# EVK-NORA-W1_SCHEM_0004_Interface_FTDI.net
KiCad netlist of a schematic drawn in Altium Designer
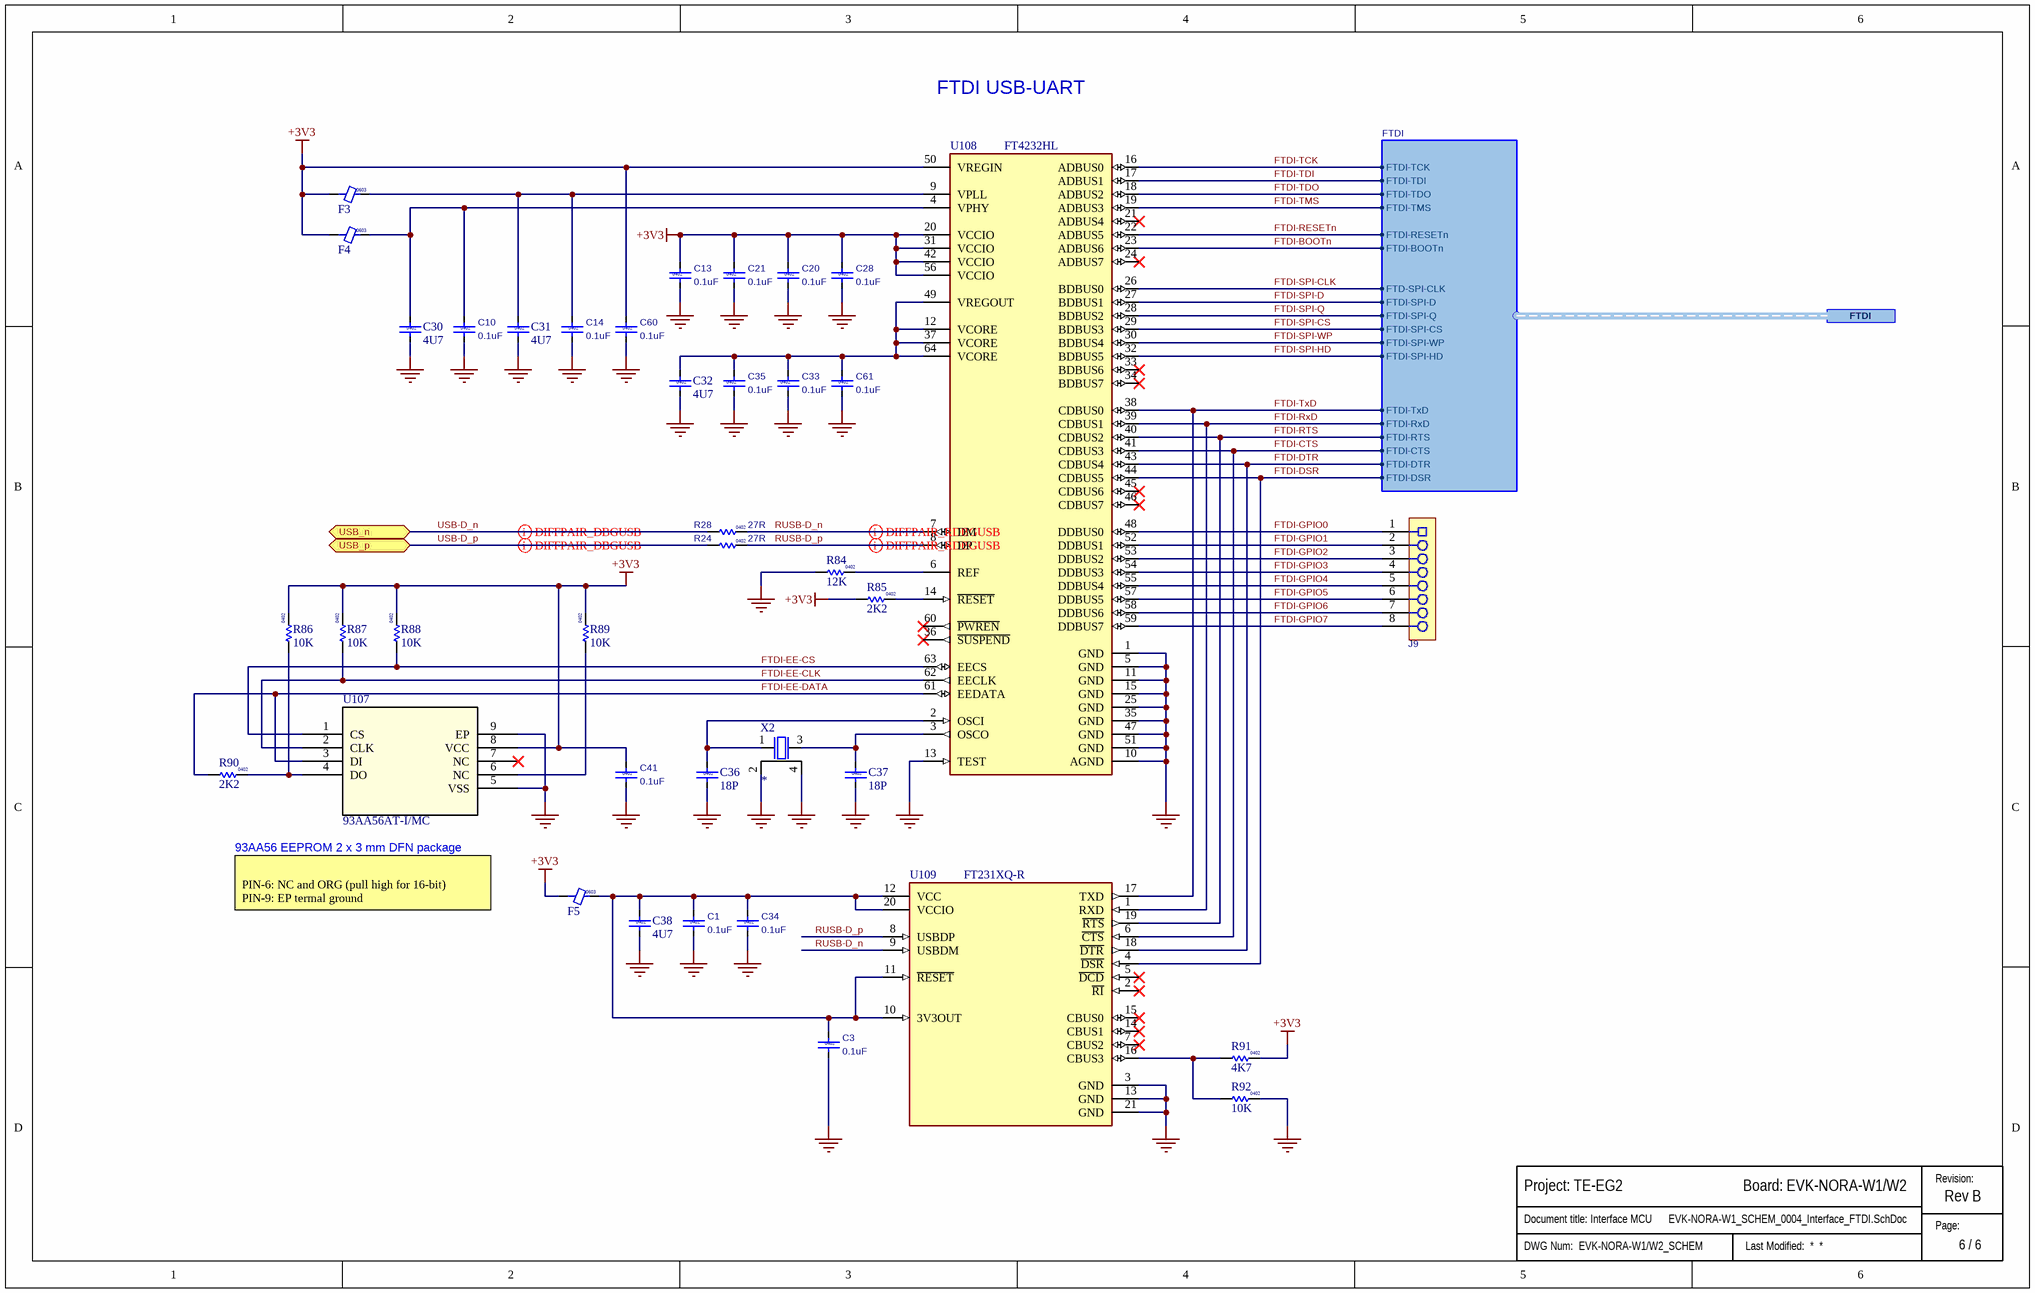
[diagram p0: EVK-NORA-W1_SCHEM_0004_Interface_FTDI.SchDoc]

(export (version "E")
  (design (tool "Eeschema 10.0.6"))
  (components
    (comp (ref "C1")
      (value "0.1uF")
      (footprint "Cap 0402 HD")
      (description "Cap, Ceramic 0.1uF 10V 10% X5R 0402")
      (fields
        (field (name "SIZE") "0402")
        (field (name "PART NUMBER") "120-00016")
        (field (name "MANUFACTURER") "Murata Electronics North America")
      )
      (libsource (lib "Arena_Parts_DB_Lib") (part "Cap Chip"))
    )
    (comp (ref "C3")
      (value "0.1uF")
      (footprint "Cap 0402 HD")
      (description "Cap, Ceramic 0.1uF 10V 10% X5R 0402")
      (fields
        (field (name "SIZE") "0402")
        (field (name "PART NUMBER") "120-00016")
        (field (name "MANUFACTURER") "Murata Electronics North America")
      )
      (libsource (lib "Arena_Parts_DB_Lib") (part "Cap Chip"))
    )
    (comp (ref "C10")
      (value "0.1uF")
      (footprint "Cap 0402 HD")
      (description "Cap, Ceramic 0.1uF 10V 10% X5R 0402")
      (fields
        (field (name "SIZE") "0402")
        (field (name "PART NUMBER") "120-00016")
        (field (name "MANUFACTURER") "Murata Electronics North America")
      )
      (libsource (lib "Arena_Parts_DB_Lib") (part "Cap Chip"))
    )
    (comp (ref "C13")
      (value "0.1uF")
      (footprint "Cap 0402 HD")
      (description "Cap, Ceramic 0.1uF 10V 10% X5R 0402")
      (fields
        (field (name "SIZE") "0402")
        (field (name "PART NUMBER") "120-00016")
        (field (name "MANUFACTURER") "Murata Electronics North America")
      )
      (libsource (lib "Arena_Parts_DB_Lib") (part "Cap Chip"))
    )
    (comp (ref "C14")
      (value "0.1uF")
      (footprint "Cap 0402 HD")
      (description "Cap, Ceramic 0.1uF 10V 10% X5R 0402")
      (fields
        (field (name "SIZE") "0402")
        (field (name "PART NUMBER") "120-00016")
        (field (name "MANUFACTURER") "Murata Electronics North America")
      )
      (libsource (lib "Arena_Parts_DB_Lib") (part "Cap Chip"))
    )
    (comp (ref "C20")
      (value "0.1uF")
      (footprint "Cap 0402 HD")
      (description "Cap, Ceramic 0.1uF 10V 10% X5R 0402")
      (fields
        (field (name "SIZE") "0402")
        (field (name "PART NUMBER") "120-00016")
        (field (name "MANUFACTURER") "Murata Electronics North America")
      )
      (libsource (lib "Arena_Parts_DB_Lib") (part "Cap Chip"))
    )
    (comp (ref "C21")
      (value "0.1uF")
      (footprint "Cap 0402 HD")
      (description "Cap, Ceramic 0.1uF 10V 10% X5R 0402")
      (fields
        (field (name "SIZE") "0402")
        (field (name "PART NUMBER") "120-00016")
        (field (name "MANUFACTURER") "Murata Electronics North America")
      )
      (libsource (lib "Arena_Parts_DB_Lib") (part "Cap Chip"))
    )
    (comp (ref "C28")
      (value "0.1uF")
      (footprint "Cap 0402 HD")
      (description "Cap, Ceramic 0.1uF 10V 10% X5R 0402")
      (fields
        (field (name "SIZE") "0402")
        (field (name "PART NUMBER") "120-00016")
        (field (name "MANUFACTURER") "Murata Electronics North America")
      )
      (libsource (lib "Arena_Parts_DB_Lib") (part "Cap Chip"))
    )
    (comp (ref "C30")
      (value "4U7")
      (footprint "Cap 0402 HD")
      (description "CAP CER X5R 0402 4U7 20% 10V")
      (fields
        (field (name "SIZE") "0402")
        (field (name "PART NUMBER") "UBXH01-0000243")
        (field (name "TOLERANCE") "20%")
        (field (name "EDITOR") "martin.pilik")
        (field (name "RELEASED BY") "fabrice.bret-dibat")
      )
      (libsource (lib "UBX_Parts_DB_Lib") (part "Cap Chip"))
    )
    (comp (ref "C31")
      (value "4U7")
      (footprint "Cap 0402 HD")
      (description "CAP CER X5R 0402 4U7 20% 10V")
      (fields
        (field (name "SIZE") "0402")
        (field (name "PART NUMBER") "UBXH01-0000243")
        (field (name "TOLERANCE") "20%")
        (field (name "EDITOR") "martin.pilik")
        (field (name "RELEASED BY") "fabrice.bret-dibat")
      )
      (libsource (lib "UBX_Parts_DB_Lib") (part "Cap Chip"))
    )
    (comp (ref "C32")
      (value "4U7")
      (footprint "Cap 0402 HD")
      (description "CAP CER X5R 0402 4U7 20% 10V")
      (fields
        (field (name "SIZE") "0402")
        (field (name "PART NUMBER") "UBXH01-0000243")
        (field (name "TOLERANCE") "20%")
        (field (name "EDITOR") "martin.pilik")
        (field (name "RELEASED BY") "fabrice.bret-dibat")
      )
      (libsource (lib "UBX_Parts_DB_Lib") (part "Cap Chip"))
    )
    (comp (ref "C33")
      (value "0.1uF")
      (footprint "Cap 0402 HD")
      (description "Cap, Ceramic 0.1uF 10V 10% X5R 0402")
      (fields
        (field (name "SIZE") "0402")
        (field (name "PART NUMBER") "120-00016")
        (field (name "MANUFACTURER") "Murata Electronics North America")
      )
      (libsource (lib "Arena_Parts_DB_Lib") (part "Cap Chip"))
    )
    (comp (ref "C34")
      (value "0.1uF")
      (footprint "Cap 0402 HD")
      (description "Cap, Ceramic 0.1uF 10V 10% X5R 0402")
      (fields
        (field (name "SIZE") "0402")
        (field (name "PART NUMBER") "120-00016")
        (field (name "MANUFACTURER") "Murata Electronics North America")
      )
      (libsource (lib "Arena_Parts_DB_Lib") (part "Cap Chip"))
    )
    (comp (ref "C35")
      (value "0.1uF")
      (footprint "Cap 0402 HD")
      (description "Cap, Ceramic 0.1uF 10V 10% X5R 0402")
      (fields
        (field (name "SIZE") "0402")
        (field (name "PART NUMBER") "120-00016")
        (field (name "MANUFACTURER") "Murata Electronics North America")
      )
      (libsource (lib "Arena_Parts_DB_Lib") (part "Cap Chip"))
    )
    (comp (ref "C36")
      (value "18P")
      (footprint "Cap 0402")
      (description "CAP CER C0G 0402 18P 5% 25V")
      (fields
        (field (name "SIZE") "0402")
        (field (name "PART NUMBER") "UBXH01-0004017")
        (field (name "TOLERANCE") "5%")
        (field (name "EDITOR") "doris.zahnd")
        (field (name "RELEASED BY") "daniel.hurni")
      )
      (libsource (lib "UBX_Parts_DB_Lib") (part "Cap Chip"))
    )
    (comp (ref "C37")
      (value "18P")
      (footprint "Cap 0402")
      (description "CAP CER C0G 0402 18P 5% 25V")
      (fields
        (field (name "SIZE") "0402")
        (field (name "PART NUMBER") "UBXH01-0004017")
        (field (name "TOLERANCE") "5%")
        (field (name "EDITOR") "doris.zahnd")
        (field (name "RELEASED BY") "daniel.hurni")
      )
      (libsource (lib "UBX_Parts_DB_Lib") (part "Cap Chip"))
    )
    (comp (ref "C38")
      (value "4U7")
      (footprint "Cap 0402 HD")
      (description "CAP CER X5R 0402 4U7 20% 10V")
      (fields
        (field (name "SIZE") "0402")
        (field (name "PART NUMBER") "UBXH01-0000243")
        (field (name "TOLERANCE") "20%")
        (field (name "EDITOR") "martin.pilik")
        (field (name "RELEASED BY") "fabrice.bret-dibat")
      )
      (libsource (lib "UBX_Parts_DB_Lib") (part "Cap Chip"))
    )
    (comp (ref "C41")
      (value "0.1uF")
      (footprint "Cap 0402 HD")
      (description "Cap, Ceramic 0.1uF 10V 10% X5R 0402")
      (fields
        (field (name "SIZE") "0402")
        (field (name "PART NUMBER") "120-00016")
        (field (name "MANUFACTURER") "Murata Electronics North America")
      )
      (libsource (lib "Arena_Parts_DB_Lib") (part "Cap Chip"))
    )
    (comp (ref "C60")
      (value "0.1uF")
      (footprint "Cap 0402 HD")
      (description "Cap, Ceramic 0.1uF 10V 10% X5R 0402")
      (fields
        (field (name "SIZE") "0402")
        (field (name "PART NUMBER") "120-00016")
        (field (name "MANUFACTURER") "Murata Electronics North America")
      )
      (libsource (lib "Arena_Parts_DB_Lib") (part "Cap Chip"))
    )
    (comp (ref "C61")
      (value "0.1uF")
      (footprint "Cap 0402 HD")
      (description "Cap, Ceramic 0.1uF 10V 10% X5R 0402")
      (fields
        (field (name "SIZE") "0402")
        (field (name "PART NUMBER") "120-00016")
        (field (name "MANUFACTURER") "Murata Electronics North America")
      )
      (libsource (lib "Arena_Parts_DB_Lib") (part "Cap Chip"))
    )
    (comp (ref "F3")
      (value "UBXH08-0000001")
      (footprint "IND 0603 HD")
      (description "FERRITE BEAD 0603 600 OHM AT 100MHZ 600OHM 500mA")
      (fields
        (field (name "SIZE") "0603")
        (field (name "MANUFACTURER") "TDK Corporation")
        (field (name "EDITOR") "daniel.hurni")
        (field (name "RELEASED BY") "martin.frauchiger")
      )
      (libsource (lib "UBX_Parts_DB_Lib") (part "FB sm"))
    )
    (comp (ref "F4")
      (value "UBXH08-0000001")
      (footprint "IND 0603 HD")
      (description "FERRITE BEAD 0603 600 OHM AT 100MHZ 600OHM 500mA")
      (fields
        (field (name "SIZE") "0603")
        (field (name "MANUFACTURER") "TDK Corporation")
        (field (name "EDITOR") "daniel.hurni")
        (field (name "RELEASED BY") "martin.frauchiger")
      )
      (libsource (lib "UBX_Parts_DB_Lib") (part "FB sm"))
    )
    (comp (ref "F5")
      (value "UBXH08-0000001")
      (footprint "IND 0603 HD")
      (description "FERRITE BEAD 0603 600 OHM AT 100MHZ 600OHM 500mA")
      (fields
        (field (name "SIZE") "0603")
        (field (name "MANUFACTURER") "TDK Corporation")
        (field (name "EDITOR") "daniel.hurni")
        (field (name "RELEASED BY") "martin.frauchiger")
      )
      (libsource (lib "UBX_Parts_DB_Lib") (part "FB sm"))
    )
    (comp (ref "J9")
      (value "130-00102")
      (footprint "SKT-0.1P-SSM-108-L-SV")
      (description "Socket Strip 0.1\" 8 Pin 1Row SMD Black")
      (fields (field (name "VOLTAGE") "572VDC"))
      (libsource (lib "Arena_Parts_DB_Lib") (part "CON-8Pin_1Row"))
    )
    (comp (ref "R24")
      (value "27R")
      (footprint "RES 0402 HD")
      (description "Resistor, 27ohm, 1%, 1/16W, 0402")
      (fields
        (field (name "SIZE") "0402")
        (field (name "PART NUMBER") "180-00125")
        (field (name "MANUFACTURER") "Panasonic Electronic Components")
      )
      (libsource (lib "Arena_Parts_DB_Lib") (part "Res sm"))
    )
    (comp (ref "R28")
      (value "27R")
      (footprint "RES 0402 HD")
      (description "Resistor, 27ohm, 1%, 1/16W, 0402")
      (fields
        (field (name "SIZE") "0402")
        (field (name "PART NUMBER") "180-00125")
        (field (name "MANUFACTURER") "Panasonic Electronic Components")
      )
      (libsource (lib "Arena_Parts_DB_Lib") (part "Res sm"))
    )
    (comp (ref "R84")
      (value "12K")
      (footprint "RES 0402 HD")
      (description "RES THICK FILM CHIP 0402 12K 1% 63mW")
      (fields
        (field (name "SIZE") "0402")
        (field (name "PART NUMBER") "UBXH18-0000137")
        (field (name "TOLERANCE") "1%")
        (field (name "EDITOR") "matej.budin")
        (field (name "RELEASED BY") "gabriele.capello")
      )
      (libsource (lib "UBX_Parts_DB_Lib") (part "Res sm"))
    )
    (comp (ref "R85")
      (value "2K2")
      (footprint "RES 0402 HD")
      (description "RES THICK FILM CHIP 0402 2K2 5% 100mW")
      (fields
        (field (name "SIZE") "0402")
        (field (name "PART NUMBER") "UBXH18-0008057")
        (field (name "TOLERANCE") "5%")
        (field (name "EDITOR") "roland.rust")
        (field (name "RELEASED BY") "roland.rust")
      )
      (libsource (lib "UBX_Parts_DB_Lib") (part "Res sm"))
    )
    (comp (ref "R86")
      (value "10K")
      (footprint "RES 0402 HD")
      (description "RES THICK FILM CHIP 0402 10K 5% 100mW")
      (fields
        (field (name "SIZE") "0402")
        (field (name "PART NUMBER") "UBXH18-0008073")
        (field (name "TOLERANCE") "5%")
        (field (name "EDITOR") "martin.frauchiger")
        (field (name "RELEASED BY") "martin.frauchiger")
      )
      (libsource (lib "UBX_Parts_DB_Lib") (part "Res sm"))
    )
    (comp (ref "R87")
      (value "10K")
      (footprint "RES 0402 HD")
      (description "RES THICK FILM CHIP 0402 10K 5% 100mW")
      (fields
        (field (name "SIZE") "0402")
        (field (name "PART NUMBER") "UBXH18-0008073")
        (field (name "TOLERANCE") "5%")
        (field (name "EDITOR") "martin.frauchiger")
        (field (name "RELEASED BY") "martin.frauchiger")
      )
      (libsource (lib "UBX_Parts_DB_Lib") (part "Res sm"))
    )
    (comp (ref "R88")
      (value "10K")
      (footprint "RES 0402 HD")
      (description "RES THICK FILM CHIP 0402 10K 5% 100mW")
      (fields
        (field (name "SIZE") "0402")
        (field (name "PART NUMBER") "UBXH18-0008073")
        (field (name "TOLERANCE") "5%")
        (field (name "EDITOR") "martin.frauchiger")
        (field (name "RELEASED BY") "martin.frauchiger")
      )
      (libsource (lib "UBX_Parts_DB_Lib") (part "Res sm"))
    )
    (comp (ref "R89")
      (value "10K")
      (footprint "RES 0402 HD")
      (description "RES THICK FILM CHIP 0402 10K 5% 100mW")
      (fields
        (field (name "SIZE") "0402")
        (field (name "PART NUMBER") "UBXH18-0008073")
        (field (name "TOLERANCE") "5%")
        (field (name "EDITOR") "martin.frauchiger")
        (field (name "RELEASED BY") "martin.frauchiger")
      )
      (libsource (lib "UBX_Parts_DB_Lib") (part "Res sm"))
    )
    (comp (ref "R90")
      (value "2K2")
      (footprint "RES 0402 HD")
      (description "RES THICK FILM CHIP 0402 2K2 5% 100mW")
      (fields
        (field (name "SIZE") "0402")
        (field (name "PART NUMBER") "UBXH18-0008057")
        (field (name "TOLERANCE") "5%")
        (field (name "EDITOR") "roland.rust")
        (field (name "RELEASED BY") "roland.rust")
      )
      (libsource (lib "UBX_Parts_DB_Lib") (part "Res sm"))
    )
    (comp (ref "R91")
      (value "4K7")
      (footprint "RES 0402 HD")
      (description "RES THICK FILM CHIP 0402 4K7 5% 100mW")
      (fields
        (field (name "SIZE") "0402")
        (field (name "PART NUMBER") "UBXH18-0008065")
        (field (name "TOLERANCE") "5%")
        (field (name "EDITOR") "martin.frauchiger")
        (field (name "RELEASED BY") "martin.frauchiger")
      )
      (libsource (lib "UBX_Parts_DB_Lib") (part "Res sm"))
    )
    (comp (ref "R92")
      (value "10K")
      (footprint "RES 0402 HD")
      (description "RES THICK FILM CHIP 0402 10K 5% 100mW")
      (fields
        (field (name "SIZE") "0402")
        (field (name "PART NUMBER") "UBXH18-0008073")
        (field (name "TOLERANCE") "5%")
        (field (name "EDITOR") "martin.frauchiger")
        (field (name "RELEASED BY") "martin.frauchiger")
      )
      (libsource (lib "UBX_Parts_DB_Lib") (part "Res sm"))
    )
    (comp (ref "U107")
      (value "93AA56AT-I/MC")
      (footprint "DFN0.5P-8Pin_W-Pad")
      (description "EEPROM SERIAL 2KBIT 256 X 8 1.8-5.5V DFN-8PIN-2X3MM 5.5V")
      (fields
        (field (name "PART NUMBER") "UBXH13-0000121")
        (field (name "MANUFACTURER") "Microchip")
        (field (name "COPYRIGHT") "Copyright (C) 2022 Ultra Librarian. All rights reserved.")
        (field (name "EDITOR") "hakan.ekfors")
      )
      (libsource (lib "UBX_Parts_DB_Lib") (part "93AA56AT_8pin_IMC"))
    )
    (comp (ref "U108")
      (value "FT4232HL")
      (footprint "QFP0.5P16x16-64Pin_HD")
      (description "FTDI FT4232HL QUAD HIGH SPEED USB TO MULTIPURPOSE UART LQFP-64")
      (fields
        (field (name "PART NUMBER") "UBXH10-0000092")
        (field (name "MANUFACTURER") "FTDI Future Technology Devices International")
        (field (name "EDITOR") "olof.viklund")
        (field (name "RELEASED BY") "aneeb.sohail")
      )
      (libsource (lib "UBX_Parts_DB_Lib") (part "FT4232HL"))
    )
    (comp (ref "U109")
      (value "FT231XQ-R")
      (footprint "QFN_5x5_FT231XQ")
      (description "FTDI USB TO SERIAL FULL UART INTERFACE QFN20")
      (fields
        (field (name "PART NUMBER") "UBXH10-0000054")
        (field (name "MANUFACTURER") "FTDI Future Technology Devices International")
        (field (name "EDITOR") "adam.johansson")
      )
      (libsource (lib "UBX_Parts_DB_Lib") (part "FT231XQ-R"))
    )
    (comp (ref "X2")
      (value "100-00006")
      (footprint "XTAL_3225")
      (description "XTAL, 4Pin, 12.0000MHz, 18pF, 20ppm, 4Pins")
      (fields (field (name "ALTIUM_VALUE") "*") (field (name "VOLTAGE") "None"))
      (libsource (lib "Arena_Parts_DB_Lib") (part "XTAL_4Pin"))
    )
  )
  (nets
    (net (code "2") (name "+3V3") (class "Default")
      (node (ref "C13") (pin "1") (pinfunction "1_1") (pintype "passive"))
      (node (ref "C20") (pin "1") (pinfunction "1_1") (pintype "passive"))
      (node (ref "C21") (pin "1") (pinfunction "1_1") (pintype "passive"))
      (node (ref "C28") (pin "1") (pinfunction "1_1") (pintype "passive"))
      (node (ref "C41") (pin "1") (pinfunction "1_1") (pintype "passive"))
      (node (ref "C60") (pin "1") (pinfunction "1_1") (pintype "passive"))
      (node (ref "F3") (pin "1") (pinfunction "1_1") (pintype "passive"))
      (node (ref "F4") (pin "1") (pinfunction "1_1") (pintype "passive"))
      (node (ref "F5") (pin "1") (pinfunction "1_1") (pintype "passive"))
      (node (ref "R85") (pin "1") (pinfunction "1_1") (pintype "passive"))
      (node (ref "R86") (pin "2") (pinfunction "2_2") (pintype "passive"))
      (node (ref "R87") (pin "2") (pinfunction "2_2") (pintype "passive"))
      (node (ref "R88") (pin "2") (pinfunction "2_2") (pintype "passive"))
      (node (ref "R89") (pin "2") (pinfunction "2_2") (pintype "passive"))
      (node (ref "R91") (pin "2") (pinfunction "2_2") (pintype "passive"))
      (node (ref "U107") (pin "8") (pinfunction "VCC_8") (pintype "passive"))
      (node (ref "U108") (pin "20") (pinfunction "VCCIO_20") (pintype "power_in"))
      (node (ref "U108") (pin "31") (pinfunction "VCCIO_31") (pintype "power_in"))
      (node (ref "U108") (pin "42") (pinfunction "VCCIO_42") (pintype "power_in"))
      (node (ref "U108") (pin "50") (pinfunction "VREGIN_50") (pintype "power_in"))
      (node (ref "U108") (pin "56") (pinfunction "VCCIO_56") (pintype "power_in"))
    )
    (net (code "3") (name "/FTDI-BOOTn") (class "Default")
      (node (ref "U108") (pin "23") (pinfunction "ADBUS6_23") (pintype "bidirectional"))
    )
    (net (code "4") (name "/FTDI-CTS") (class "Default")
      (node (ref "U108") (pin "41") (pinfunction "CDBUS3_41") (pintype "bidirectional"))
      (node (ref "U109") (pin "6") (pinfunction "~{CTS}_6") (pintype "input"))
    )
    (net (code "5") (name "/FTDI-DSR") (class "Default")
      (node (ref "U108") (pin "44") (pinfunction "CDBUS5_44") (pintype "bidirectional"))
      (node (ref "U109") (pin "4") (pinfunction "~{DSR}_4") (pintype "input"))
    )
    (net (code "6") (name "/FTDI-DTR") (class "Default")
      (node (ref "U108") (pin "43") (pinfunction "CDBUS4_43") (pintype "bidirectional"))
      (node (ref "U109") (pin "18") (pinfunction "~{DTR}_18") (pintype "output"))
    )
    (net (code "7") (name "/FTDI-EE-CLK") (class "Default")
      (node (ref "R87") (pin "1") (pinfunction "1_1") (pintype "passive"))
      (node (ref "U107") (pin "2") (pinfunction "CLK_2") (pintype "passive"))
      (node (ref "U108") (pin "62") (pinfunction "EECLK_62") (pintype "output"))
    )
    (net (code "8") (name "/FTDI-EE-CS") (class "Default")
      (node (ref "R88") (pin "1") (pinfunction "1_1") (pintype "passive"))
      (node (ref "U107") (pin "1") (pinfunction "CS_1") (pintype "passive"))
      (node (ref "U108") (pin "63") (pinfunction "EECS_63") (pintype "bidirectional"))
    )
    (net (code "9") (name "/FTDI-EE-DATA") (class "Default")
      (node (ref "R90") (pin "1") (pinfunction "1_1") (pintype "passive"))
      (node (ref "U107") (pin "3") (pinfunction "DI_3") (pintype "passive"))
      (node (ref "U108") (pin "61") (pinfunction "EEDATA_61") (pintype "bidirectional"))
    )
    (net (code "10") (name "/FTDI-GPIO0") (class "Default")
      (node (ref "J9") (pin "1") (pintype "passive"))
      (node (ref "U108") (pin "48") (pinfunction "DDBUS0_48") (pintype "bidirectional"))
    )
    (net (code "11") (name "/FTDI-GPIO1") (class "Default")
      (node (ref "J9") (pin "2") (pintype "passive"))
      (node (ref "U108") (pin "52") (pinfunction "DDBUS1_52") (pintype "bidirectional"))
    )
    (net (code "12") (name "/FTDI-GPIO2") (class "Default")
      (node (ref "J9") (pin "3") (pintype "passive"))
      (node (ref "U108") (pin "53") (pinfunction "DDBUS2_53") (pintype "bidirectional"))
    )
    (net (code "13") (name "/FTDI-GPIO3") (class "Default")
      (node (ref "J9") (pin "4") (pintype "passive"))
      (node (ref "U108") (pin "54") (pinfunction "DDBUS3_54") (pintype "bidirectional"))
    )
    (net (code "14") (name "/FTDI-GPIO4") (class "Default")
      (node (ref "J9") (pin "5") (pintype "passive"))
      (node (ref "U108") (pin "55") (pinfunction "DDBUS4_55") (pintype "bidirectional"))
    )
    (net (code "15") (name "/FTDI-GPIO5") (class "Default")
      (node (ref "J9") (pin "6") (pintype "passive"))
      (node (ref "U108") (pin "57") (pinfunction "DDBUS5_57") (pintype "bidirectional"))
    )
    (net (code "16") (name "/FTDI-GPIO6") (class "Default")
      (node (ref "J9") (pin "7") (pintype "passive"))
      (node (ref "U108") (pin "58") (pinfunction "DDBUS6_58") (pintype "bidirectional"))
    )
    (net (code "17") (name "/FTDI-GPIO7") (class "Default")
      (node (ref "J9") (pin "8") (pintype "passive"))
      (node (ref "U108") (pin "59") (pinfunction "DDBUS7_59") (pintype "bidirectional"))
    )
    (net (code "18") (name "/FTDI-RESETn") (class "Default")
      (node (ref "U108") (pin "22") (pinfunction "ADBUS5_22") (pintype "bidirectional"))
    )
    (net (code "19") (name "/FTDI-RTS") (class "Default")
      (node (ref "U108") (pin "40") (pinfunction "CDBUS2_40") (pintype "bidirectional"))
      (node (ref "U109") (pin "19") (pinfunction "~{RTS}_19") (pintype "output"))
    )
    (net (code "20") (name "/FTDI-RxD") (class "Default")
      (node (ref "U108") (pin "39") (pinfunction "CDBUS1_39") (pintype "bidirectional"))
      (node (ref "U109") (pin "1") (pinfunction "RXD_1") (pintype "input"))
    )
    (net (code "21") (name "/FTDI-SPI-CLK") (class "Default")
      (node (ref "U108") (pin "26") (pinfunction "BDBUS0_26") (pintype "bidirectional"))
    )
    (net (code "22") (name "/FTDI-SPI-CS") (class "Default")
      (node (ref "U108") (pin "29") (pinfunction "BDBUS3_29") (pintype "bidirectional"))
    )
    (net (code "23") (name "/FTDI-SPI-D") (class "Default")
      (node (ref "U108") (pin "27") (pinfunction "BDBUS1_27") (pintype "bidirectional"))
    )
    (net (code "24") (name "/FTDI-SPI-HD") (class "Default")
      (node (ref "U108") (pin "32") (pinfunction "BDBUS5_32") (pintype "bidirectional"))
    )
    (net (code "25") (name "/FTDI-SPI-Q") (class "Default")
      (node (ref "U108") (pin "28") (pinfunction "BDBUS2_28") (pintype "bidirectional"))
    )
    (net (code "26") (name "/FTDI-SPI-WP") (class "Default")
      (node (ref "U108") (pin "30") (pinfunction "BDBUS4_30") (pintype "bidirectional"))
    )
    (net (code "27") (name "/FTDI-TCK") (class "Default")
      (node (ref "U108") (pin "16") (pinfunction "ADBUS0_16") (pintype "bidirectional"))
    )
    (net (code "28") (name "/FTDI-TDI") (class "Default")
      (node (ref "U108") (pin "17") (pinfunction "ADBUS1_17") (pintype "bidirectional"))
    )
    (net (code "29") (name "/FTDI-TDO") (class "Default")
      (node (ref "U108") (pin "18") (pinfunction "ADBUS2_18") (pintype "bidirectional"))
    )
    (net (code "30") (name "/FTDI-TMS") (class "Default")
      (node (ref "U108") (pin "19") (pinfunction "ADBUS3_19") (pintype "bidirectional"))
    )
    (net (code "31") (name "/FTDI-TxD") (class "Default")
      (node (ref "U108") (pin "38") (pinfunction "CDBUS0_38") (pintype "bidirectional"))
      (node (ref "U109") (pin "17") (pinfunction "TXD_17") (pintype "output"))
    )
    (net (code "32") (name "/RUSB-D_n") (class "Default")
      (node (ref "R28") (pin "1") (pinfunction "1_1") (pintype "passive"))
      (node (ref "U108") (pin "7") (pinfunction "DM_7") (pintype "bidirectional"))
      (node (ref "U109") (pin "9") (pinfunction "USBDM_9") (pintype "input"))
    )
    (net (code "33") (name "/RUSB-D_p") (class "Default")
      (node (ref "R24") (pin "1") (pinfunction "1_1") (pintype "passive"))
      (node (ref "U108") (pin "8") (pinfunction "DP_8") (pintype "bidirectional"))
      (node (ref "U109") (pin "8") (pinfunction "USBDP_8") (pintype "input"))
    )
    (net (code "34") (name "/USB-D_n") (class "Default")
      (node (ref "R28") (pin "2") (pinfunction "2_2") (pintype "passive"))
    )
    (net (code "35") (name "/USB-D_p") (class "Default")
      (node (ref "R24") (pin "2") (pinfunction "2_2") (pintype "passive"))
    )
    (net (code "37") (name "GND") (class "Default")
      (node (ref "C1") (pin "2") (pinfunction "2_2") (pintype "passive"))
      (node (ref "C10") (pin "2") (pinfunction "2_2") (pintype "passive"))
      (node (ref "C13") (pin "2") (pinfunction "2_2") (pintype "passive"))
      (node (ref "C14") (pin "2") (pinfunction "2_2") (pintype "passive"))
      (node (ref "C20") (pin "2") (pinfunction "2_2") (pintype "passive"))
      (node (ref "C21") (pin "2") (pinfunction "2_2") (pintype "passive"))
      (node (ref "C28") (pin "2") (pinfunction "2_2") (pintype "passive"))
      (node (ref "C3") (pin "2") (pinfunction "2_2") (pintype "passive"))
      (node (ref "C30") (pin "2") (pinfunction "2_2") (pintype "passive"))
      (node (ref "C31") (pin "2") (pinfunction "2_2") (pintype "passive"))
      (node (ref "C32") (pin "2") (pinfunction "2_2") (pintype "passive"))
      (node (ref "C33") (pin "2") (pinfunction "2_2") (pintype "passive"))
      (node (ref "C34") (pin "2") (pinfunction "2_2") (pintype "passive"))
      (node (ref "C35") (pin "2") (pinfunction "2_2") (pintype "passive"))
      (node (ref "C36") (pin "2") (pinfunction "2_2") (pintype "passive"))
      (node (ref "C37") (pin "2") (pinfunction "2_2") (pintype "passive"))
      (node (ref "C38") (pin "2") (pinfunction "2_2") (pintype "passive"))
      (node (ref "C41") (pin "2") (pinfunction "2_2") (pintype "passive"))
      (node (ref "C60") (pin "2") (pinfunction "2_2") (pintype "passive"))
      (node (ref "C61") (pin "2") (pinfunction "2_2") (pintype "passive"))
      (node (ref "R84") (pin "1") (pinfunction "1_1") (pintype "passive"))
      (node (ref "R92") (pin "2") (pinfunction "2_2") (pintype "passive"))
      (node (ref "U107") (pin "5") (pinfunction "VSS_5") (pintype "passive"))
      (node (ref "U107") (pin "9") (pinfunction "EP_9") (pintype "passive"))
      (node (ref "U108") (pin "1") (pinfunction "GND_1") (pintype "power_in"))
      (node (ref "U108") (pin "10") (pinfunction "AGND_10") (pintype "power_in"))
      (node (ref "U108") (pin "11") (pinfunction "GND_11") (pintype "power_in"))
      (node (ref "U108") (pin "13") (pinfunction "TEST_13") (pintype "input"))
      (node (ref "U108") (pin "15") (pinfunction "GND_15") (pintype "power_in"))
      (node (ref "U108") (pin "25") (pinfunction "GND_25") (pintype "power_in"))
      (node (ref "U108") (pin "35") (pinfunction "GND_35") (pintype "power_in"))
      (node (ref "U108") (pin "47") (pinfunction "GND_47") (pintype "power_in"))
      (node (ref "U108") (pin "5") (pinfunction "GND_5") (pintype "power_in"))
      (node (ref "U108") (pin "51") (pinfunction "GND_51") (pintype "power_in"))
      (node (ref "U109") (pin "13") (pinfunction "GND_13") (pintype "power_in"))
      (node (ref "U109") (pin "21") (pinfunction "GND_21") (pintype "power_in"))
      (node (ref "U109") (pin "3") (pinfunction "GND_3") (pintype "power_in"))
      (node (ref "X2") (pin "2") (pintype "passive"))
      (node (ref "X2") (pin "4") (pintype "passive"))
    )
    (net (code "38") (name "Net-(R89-Pad1)") (class "Default")
      (node (ref "R89") (pin "1") (pinfunction "1_1") (pintype "passive"))
      (node (ref "U107") (pin "6") (pinfunction "NC_6") (pintype "passive"))
    )
    (net (code "39") (name "Net-(U107-DO)") (class "Default")
      (node (ref "R86") (pin "1") (pinfunction "1_1") (pintype "passive"))
      (node (ref "R90") (pin "2") (pinfunction "2_2") (pintype "passive"))
      (node (ref "U107") (pin "4") (pinfunction "DO_4") (pintype "passive"))
    )
    (net (code "40") (name "Net-(U108-OSCI)") (class "Default")
      (node (ref "C36") (pin "1") (pinfunction "1_1") (pintype "passive"))
      (node (ref "U108") (pin "2") (pinfunction "OSCI_2") (pintype "input"))
      (node (ref "X2") (pin "1") (pintype "passive"))
    )
    (net (code "41") (name "Net-(U108-OSCO)") (class "Default")
      (node (ref "C37") (pin "1") (pinfunction "1_1") (pintype "passive"))
      (node (ref "U108") (pin "3") (pinfunction "OSCO_3") (pintype "output"))
      (node (ref "X2") (pin "3") (pintype "passive"))
    )
    (net (code "42") (name "Net-(U108-REF)") (class "Default")
      (node (ref "R84") (pin "2") (pinfunction "2_2") (pintype "passive"))
      (node (ref "U108") (pin "6") (pinfunction "REF_6") (pintype "passive"))
    )
    (net (code "43") (name "Net-(U108-VPHY)") (class "Default")
      (node (ref "C10") (pin "1") (pinfunction "1_1") (pintype "passive"))
      (node (ref "C30") (pin "1") (pinfunction "1_1") (pintype "passive"))
      (node (ref "F4") (pin "2") (pinfunction "2_2") (pintype "passive"))
      (node (ref "U108") (pin "4") (pinfunction "VPHY_4") (pintype "power_in"))
    )
    (net (code "44") (name "Net-(U108-VPLL)") (class "Default")
      (node (ref "C14") (pin "1") (pinfunction "1_1") (pintype "passive"))
      (node (ref "C31") (pin "1") (pinfunction "1_1") (pintype "passive"))
      (node (ref "F3") (pin "2") (pinfunction "2_2") (pintype "passive"))
      (node (ref "U108") (pin "9") (pinfunction "VPLL_9") (pintype "power_in"))
    )
    (net (code "45") (name "Net-(U108-VREGOUT)") (class "Default")
      (node (ref "C32") (pin "1") (pinfunction "1_1") (pintype "passive"))
      (node (ref "C33") (pin "1") (pinfunction "1_1") (pintype "passive"))
      (node (ref "C35") (pin "1") (pinfunction "1_1") (pintype "passive"))
      (node (ref "C61") (pin "1") (pinfunction "1_1") (pintype "passive"))
      (node (ref "U108") (pin "12") (pinfunction "VCORE_12") (pintype "power_in"))
      (node (ref "U108") (pin "37") (pinfunction "VCORE_37") (pintype "power_in"))
      (node (ref "U108") (pin "49") (pinfunction "VREGOUT_49") (pintype "power_in"))
      (node (ref "U108") (pin "64") (pinfunction "VCORE_64") (pintype "power_in"))
    )
    (net (code "46") (name "Net-(U108-~{RESET})") (class "Default")
      (node (ref "R85") (pin "2") (pinfunction "2_2") (pintype "passive"))
      (node (ref "U108") (pin "14") (pinfunction "~{RESET}_14") (pintype "input"))
    )
    (net (code "47") (name "Net-(U109-3V3OUT)") (class "Default")
      (node (ref "C1") (pin "1") (pinfunction "1_1") (pintype "passive"))
      (node (ref "C3") (pin "1") (pinfunction "1_1") (pintype "passive"))
      (node (ref "C34") (pin "1") (pinfunction "1_1") (pintype "passive"))
      (node (ref "C38") (pin "1") (pinfunction "1_1") (pintype "passive"))
      (node (ref "F5") (pin "2") (pinfunction "2_2") (pintype "passive"))
      (node (ref "U109") (pin "10") (pinfunction "3V3OUT_10") (pintype "input"))
      (node (ref "U109") (pin "11") (pinfunction "~{RESET}_11") (pintype "input"))
      (node (ref "U109") (pin "12") (pinfunction "VCC_12") (pintype "power_in"))
      (node (ref "U109") (pin "20") (pinfunction "VCCIO_20") (pintype "power_in"))
    )
    (net (code "48") (name "Net-(U109-CBUS3)") (class "Default")
      (node (ref "R91") (pin "1") (pinfunction "1_1") (pintype "passive"))
      (node (ref "R92") (pin "1") (pinfunction "1_1") (pintype "passive"))
      (node (ref "U109") (pin "16") (pinfunction "CBUS3_16") (pintype "bidirectional"))
    )
    (net (code "49") (name "unconnected-(U107-NC-Pad7)") (class "Default")
      (node (ref "U107") (pin "7") (pinfunction "NC_7") (pintype "passive+no_connect"))
    )
    (net (code "50") (name "unconnected-(U108-ADBUS4-Pad21)") (class "Default")
      (node (ref "U108") (pin "21") (pinfunction "ADBUS4_21") (pintype "bidirectional+no_connect"))
    )
    (net (code "51") (name "unconnected-(U108-ADBUS7-Pad24)") (class "Default")
      (node (ref "U108") (pin "24") (pinfunction "ADBUS7_24") (pintype "bidirectional+no_connect"))
    )
    (net (code "52") (name "unconnected-(U108-BDBUS6-Pad33)") (class "Default")
      (node (ref "U108") (pin "33") (pinfunction "BDBUS6_33") (pintype "bidirectional+no_connect"))
    )
    (net (code "53") (name "unconnected-(U108-BDBUS7-Pad34)") (class "Default")
      (node (ref "U108") (pin "34") (pinfunction "BDBUS7_34") (pintype "bidirectional+no_connect"))
    )
    (net (code "54") (name "unconnected-(U108-CDBUS6-Pad45)") (class "Default")
      (node (ref "U108") (pin "45") (pinfunction "CDBUS6_45") (pintype "bidirectional+no_connect"))
    )
    (net (code "55") (name "unconnected-(U108-CDBUS7-Pad46)") (class "Default")
      (node (ref "U108") (pin "46") (pinfunction "CDBUS7_46") (pintype "bidirectional+no_connect"))
    )
    (net (code "56") (name "unconnected-(U108-~{PWREN}-Pad60)") (class "Default")
      (node (ref "U108") (pin "60") (pinfunction "~{PWREN}_60") (pintype "output+no_connect"))
    )
    (net (code "57") (name "unconnected-(U108-~{SUSPEND}-Pad36)") (class "Default")
      (node (ref "U108") (pin "36") (pinfunction "~{SUSPEND}_36") (pintype "output+no_connect"))
    )
    (net (code "58") (name "unconnected-(U109-CBUS0-Pad15)") (class "Default")
      (node (ref "U109") (pin "15") (pinfunction "CBUS0_15") (pintype "bidirectional+no_connect"))
    )
    (net (code "59") (name "unconnected-(U109-CBUS1-Pad14)") (class "Default")
      (node (ref "U109") (pin "14") (pinfunction "CBUS1_14") (pintype "bidirectional+no_connect"))
    )
    (net (code "60") (name "unconnected-(U109-CBUS2-Pad7)") (class "Default")
      (node (ref "U109") (pin "7") (pinfunction "CBUS2_7") (pintype "bidirectional+no_connect"))
    )
    (net (code "61") (name "unconnected-(U109-~{DCD}-Pad5)") (class "Default")
      (node (ref "U109") (pin "5") (pinfunction "~{DCD}_5") (pintype "input+no_connect"))
    )
    (net (code "62") (name "unconnected-(U109-~{RI}-Pad2)") (class "Default")
      (node (ref "U109") (pin "2") (pinfunction "~{RI}_2") (pintype "input+no_connect"))
    )
  )
)
